# DRIVER_L293D.net
KiCad netlist of a schematic drawn in EAGLE
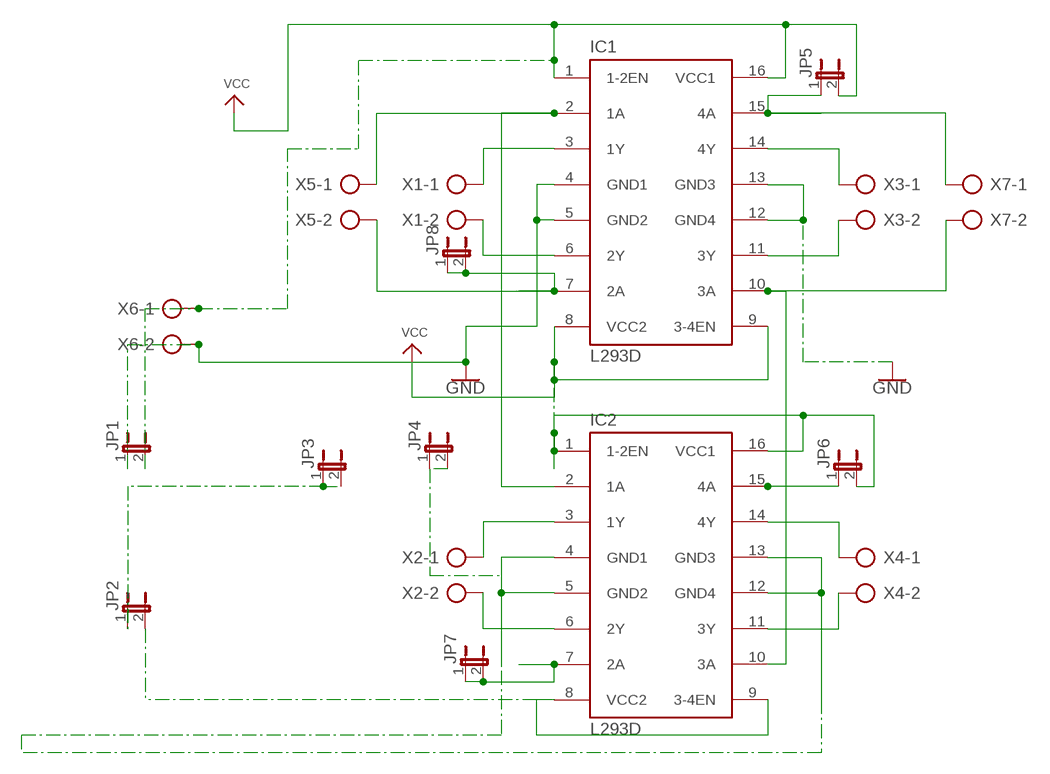
[diagram p0: schematic, sheet 1]

(export (version "E")
  (design (tool "Eeschema 10.0.6"))
  (components
    (comp (ref "IC1")
      (value "L293D")
      (footprint "eagle-import:DIL16")
      (libsource (lib "eagle-import") (part "L293D"))
    )
    (comp (ref "IC2")
      (value "L293D")
      (footprint "eagle-import:DIL16")
      (libsource (lib "eagle-import") (part "L293D"))
    )
    (comp (ref "JP1")
      (value "JP1E")
      (footprint "eagle-import:JP1")
      (libsource (lib "eagle-import") (part "JP1E"))
    )
    (comp (ref "JP2")
      (value "JP1E")
      (footprint "eagle-import:JP1")
      (libsource (lib "eagle-import") (part "JP1E"))
    )
    (comp (ref "JP3")
      (value "JP1E")
      (footprint "eagle-import:JP1")
      (libsource (lib "eagle-import") (part "JP1E"))
    )
    (comp (ref "JP4")
      (value "JP1E")
      (footprint "eagle-import:JP1")
      (libsource (lib "eagle-import") (part "JP1E"))
    )
    (comp (ref "JP5")
      (value "JP1E")
      (footprint "eagle-import:JP1")
      (libsource (lib "eagle-import") (part "JP1E"))
    )
    (comp (ref "JP6")
      (value "JP1E")
      (footprint "eagle-import:JP1")
      (libsource (lib "eagle-import") (part "JP1E"))
    )
    (comp (ref "JP7")
      (value "JP1E")
      (footprint "eagle-import:JP1")
      (libsource (lib "eagle-import") (part "JP1E"))
    )
    (comp (ref "JP8")
      (value "JP1E")
      (footprint "eagle-import:JP1")
      (libsource (lib "eagle-import") (part "JP1E"))
    )
    (comp (ref "X1")
      (value "AK500/2-H")
      (footprint "eagle-import:AK500_2-H")
      (libsource (lib "eagle-import") (part "AK500/2-H"))
    )
    (comp (ref "X2")
      (value "AK500/2-H")
      (footprint "eagle-import:AK500_2-H")
      (libsource (lib "eagle-import") (part "AK500/2-H"))
    )
    (comp (ref "X3")
      (value "AK500/2-H")
      (footprint "eagle-import:AK500_2-H")
      (libsource (lib "eagle-import") (part "AK500/2-H"))
    )
    (comp (ref "X4")
      (value "AK500/2-H")
      (footprint "eagle-import:AK500_2-H")
      (libsource (lib "eagle-import") (part "AK500/2-H"))
    )
    (comp (ref "X5")
      (value "AK500/2-H")
      (footprint "eagle-import:AK500_2-H")
      (libsource (lib "eagle-import") (part "AK500/2-H"))
    )
    (comp (ref "X6")
      (value "AK500/2-H")
      (footprint "eagle-import:AK500_2-H")
      (libsource (lib "eagle-import") (part "AK500/2-H"))
    )
    (comp (ref "X7")
      (value "AK500/2-H")
      (footprint "eagle-import:AK500_2-H")
      (libsource (lib "eagle-import") (part "AK500/2-H"))
    )
  )
  (nets
    (net (code "1") (name "GND") (class "Default")
      (node (ref "IC1") (pin "12") (pinfunction "GND4_12") (pintype "power_in"))
      (node (ref "IC1") (pin "13") (pinfunction "GND3_13") (pintype "power_in"))
      (node (ref "IC1") (pin "4") (pinfunction "GND1_4") (pintype "power_in"))
      (node (ref "IC1") (pin "5") (pinfunction "GND2_5") (pintype "power_in"))
      (node (ref "JP1") (pin "1") (pinfunction "1_1") (pintype "passive"))
      (node (ref "X6") (pin "2") (pinfunction "KL_2") (pintype "passive"))
    )
    (net (code "2") (name "Net-(IC1-1A)") (class "Default")
      (node (ref "IC1") (pin "2") (pinfunction "1A_2") (pintype "input"))
      (node (ref "IC2") (pin "2") (pinfunction "1A_2") (pintype "input"))
      (node (ref "X5") (pin "1") (pinfunction "KL_1") (pintype "passive"))
    )
    (net (code "3") (name "Net-(IC1-1Y)") (class "Default")
      (node (ref "IC1") (pin "3") (pinfunction "1Y_3") (pintype "output"))
      (node (ref "X1") (pin "1") (pinfunction "KL_1") (pintype "passive"))
    )
    (net (code "4") (name "Net-(IC1-2A)") (class "Default")
      (node (ref "IC1") (pin "7") (pinfunction "2A_7") (pintype "input"))
      (node (ref "JP8") (pin "1") (pinfunction "1_1") (pintype "passive"))
      (node (ref "JP8") (pin "2") (pinfunction "2_2") (pintype "passive"))
      (node (ref "X5") (pin "2") (pinfunction "KL_2") (pintype "passive"))
    )
    (net (code "5") (name "Net-(IC1-2Y)") (class "Default")
      (node (ref "IC1") (pin "6") (pinfunction "2Y_6") (pintype "output"))
      (node (ref "X1") (pin "2") (pinfunction "KL_2") (pintype "passive"))
    )
    (net (code "6") (name "Net-(IC1-3A)") (class "Default")
      (node (ref "IC1") (pin "10") (pinfunction "3A_10") (pintype "input"))
      (node (ref "IC2") (pin "10") (pinfunction "3A_10") (pintype "input"))
      (node (ref "X7") (pin "2") (pinfunction "KL_2") (pintype "passive"))
    )
    (net (code "7") (name "Net-(IC1-3Y)") (class "Default")
      (node (ref "IC1") (pin "11") (pinfunction "3Y_11") (pintype "output"))
      (node (ref "X3") (pin "2") (pinfunction "KL_2") (pintype "passive"))
    )
    (net (code "8") (name "Net-(IC1-4A)") (class "Default")
      (node (ref "IC1") (pin "15") (pinfunction "4A_15") (pintype "input"))
      (node (ref "JP5") (pin "1") (pinfunction "1_1") (pintype "passive"))
      (node (ref "X7") (pin "1") (pinfunction "KL_1") (pintype "passive"))
    )
    (net (code "9") (name "Net-(IC1-4Y)") (class "Default")
      (node (ref "IC1") (pin "14") (pinfunction "4Y_14") (pintype "output"))
      (node (ref "X3") (pin "1") (pinfunction "KL_1") (pintype "passive"))
    )
    (net (code "10") (name "Net-(IC2-1Y)") (class "Default")
      (node (ref "IC2") (pin "3") (pinfunction "1Y_3") (pintype "output"))
      (node (ref "X2") (pin "1") (pinfunction "KL_1") (pintype "passive"))
    )
    (net (code "11") (name "Net-(IC2-2A)") (class "Default")
      (node (ref "IC2") (pin "7") (pinfunction "2A_7") (pintype "input"))
      (node (ref "JP7") (pin "1") (pinfunction "1_1") (pintype "passive"))
      (node (ref "JP7") (pin "2") (pinfunction "2_2") (pintype "passive"))
    )
    (net (code "12") (name "Net-(IC2-2Y)") (class "Default")
      (node (ref "IC2") (pin "6") (pinfunction "2Y_6") (pintype "output"))
      (node (ref "X2") (pin "2") (pinfunction "KL_2") (pintype "passive"))
    )
    (net (code "13") (name "Net-(IC2-3-4EN)") (class "Default")
      (node (ref "IC2") (pin "8") (pinfunction "VCC2_8") (pintype "power_in"))
      (node (ref "IC2") (pin "9") (pinfunction "3-4EN_9") (pintype "input"))
      (node (ref "JP2") (pin "2") (pinfunction "2_2") (pintype "passive"))
    )
    (net (code "14") (name "Net-(IC2-3Y)") (class "Default")
      (node (ref "IC2") (pin "11") (pinfunction "3Y_11") (pintype "output"))
      (node (ref "X4") (pin "2") (pinfunction "KL_2") (pintype "passive"))
    )
    (net (code "15") (name "Net-(IC2-4A)") (class "Default")
      (node (ref "IC2") (pin "15") (pinfunction "4A_15") (pintype "input"))
      (node (ref "JP6") (pin "1") (pinfunction "1_1") (pintype "passive"))
    )
    (net (code "16") (name "Net-(IC2-4Y)") (class "Default")
      (node (ref "IC2") (pin "14") (pinfunction "4Y_14") (pintype "output"))
      (node (ref "X4") (pin "1") (pinfunction "KL_1") (pintype "passive"))
    )
    (net (code "17") (name "Net-(IC2-GND1)") (class "Default")
      (node (ref "IC2") (pin "12") (pinfunction "GND4_12") (pintype "power_in"))
      (node (ref "IC2") (pin "13") (pinfunction "GND3_13") (pintype "power_in"))
      (node (ref "IC2") (pin "4") (pinfunction "GND1_4") (pintype "power_in"))
      (node (ref "IC2") (pin "5") (pinfunction "GND2_5") (pintype "power_in"))
      (node (ref "JP4") (pin "1") (pinfunction "1_1") (pintype "passive"))
      (node (ref "JP4") (pin "2") (pinfunction "2_2") (pintype "passive"))
    )
    (net (code "18") (name "Net-(JP2-Pad1)") (class "Default")
      (node (ref "JP2") (pin "1") (pinfunction "1_1") (pintype "passive"))
      (node (ref "JP3") (pin "1") (pinfunction "1_1") (pintype "passive"))
      (node (ref "JP3") (pin "2") (pinfunction "2_2") (pintype "passive"))
    )
    (net (code "19") (name "VCC") (class "Default")
      (node (ref "IC1") (pin "1") (pinfunction "1-2EN_1") (pintype "input"))
      (node (ref "IC1") (pin "16") (pinfunction "VCC1_16") (pintype "power_in"))
      (node (ref "IC1") (pin "8") (pinfunction "VCC2_8") (pintype "power_in"))
      (node (ref "IC1") (pin "9") (pinfunction "3-4EN_9") (pintype "input"))
      (node (ref "IC2") (pin "1") (pinfunction "1-2EN_1") (pintype "input"))
      (node (ref "IC2") (pin "16") (pinfunction "VCC1_16") (pintype "power_in"))
      (node (ref "JP1") (pin "2") (pinfunction "2_2") (pintype "passive"))
      (node (ref "JP5") (pin "2") (pinfunction "2_2") (pintype "passive"))
      (node (ref "JP6") (pin "2") (pinfunction "2_2") (pintype "passive"))
      (node (ref "X6") (pin "1") (pinfunction "KL_1") (pintype "passive"))
    )
  )
)
